# A-GSM.net
KiCad netlist of a schematic drawn in Altium Designer
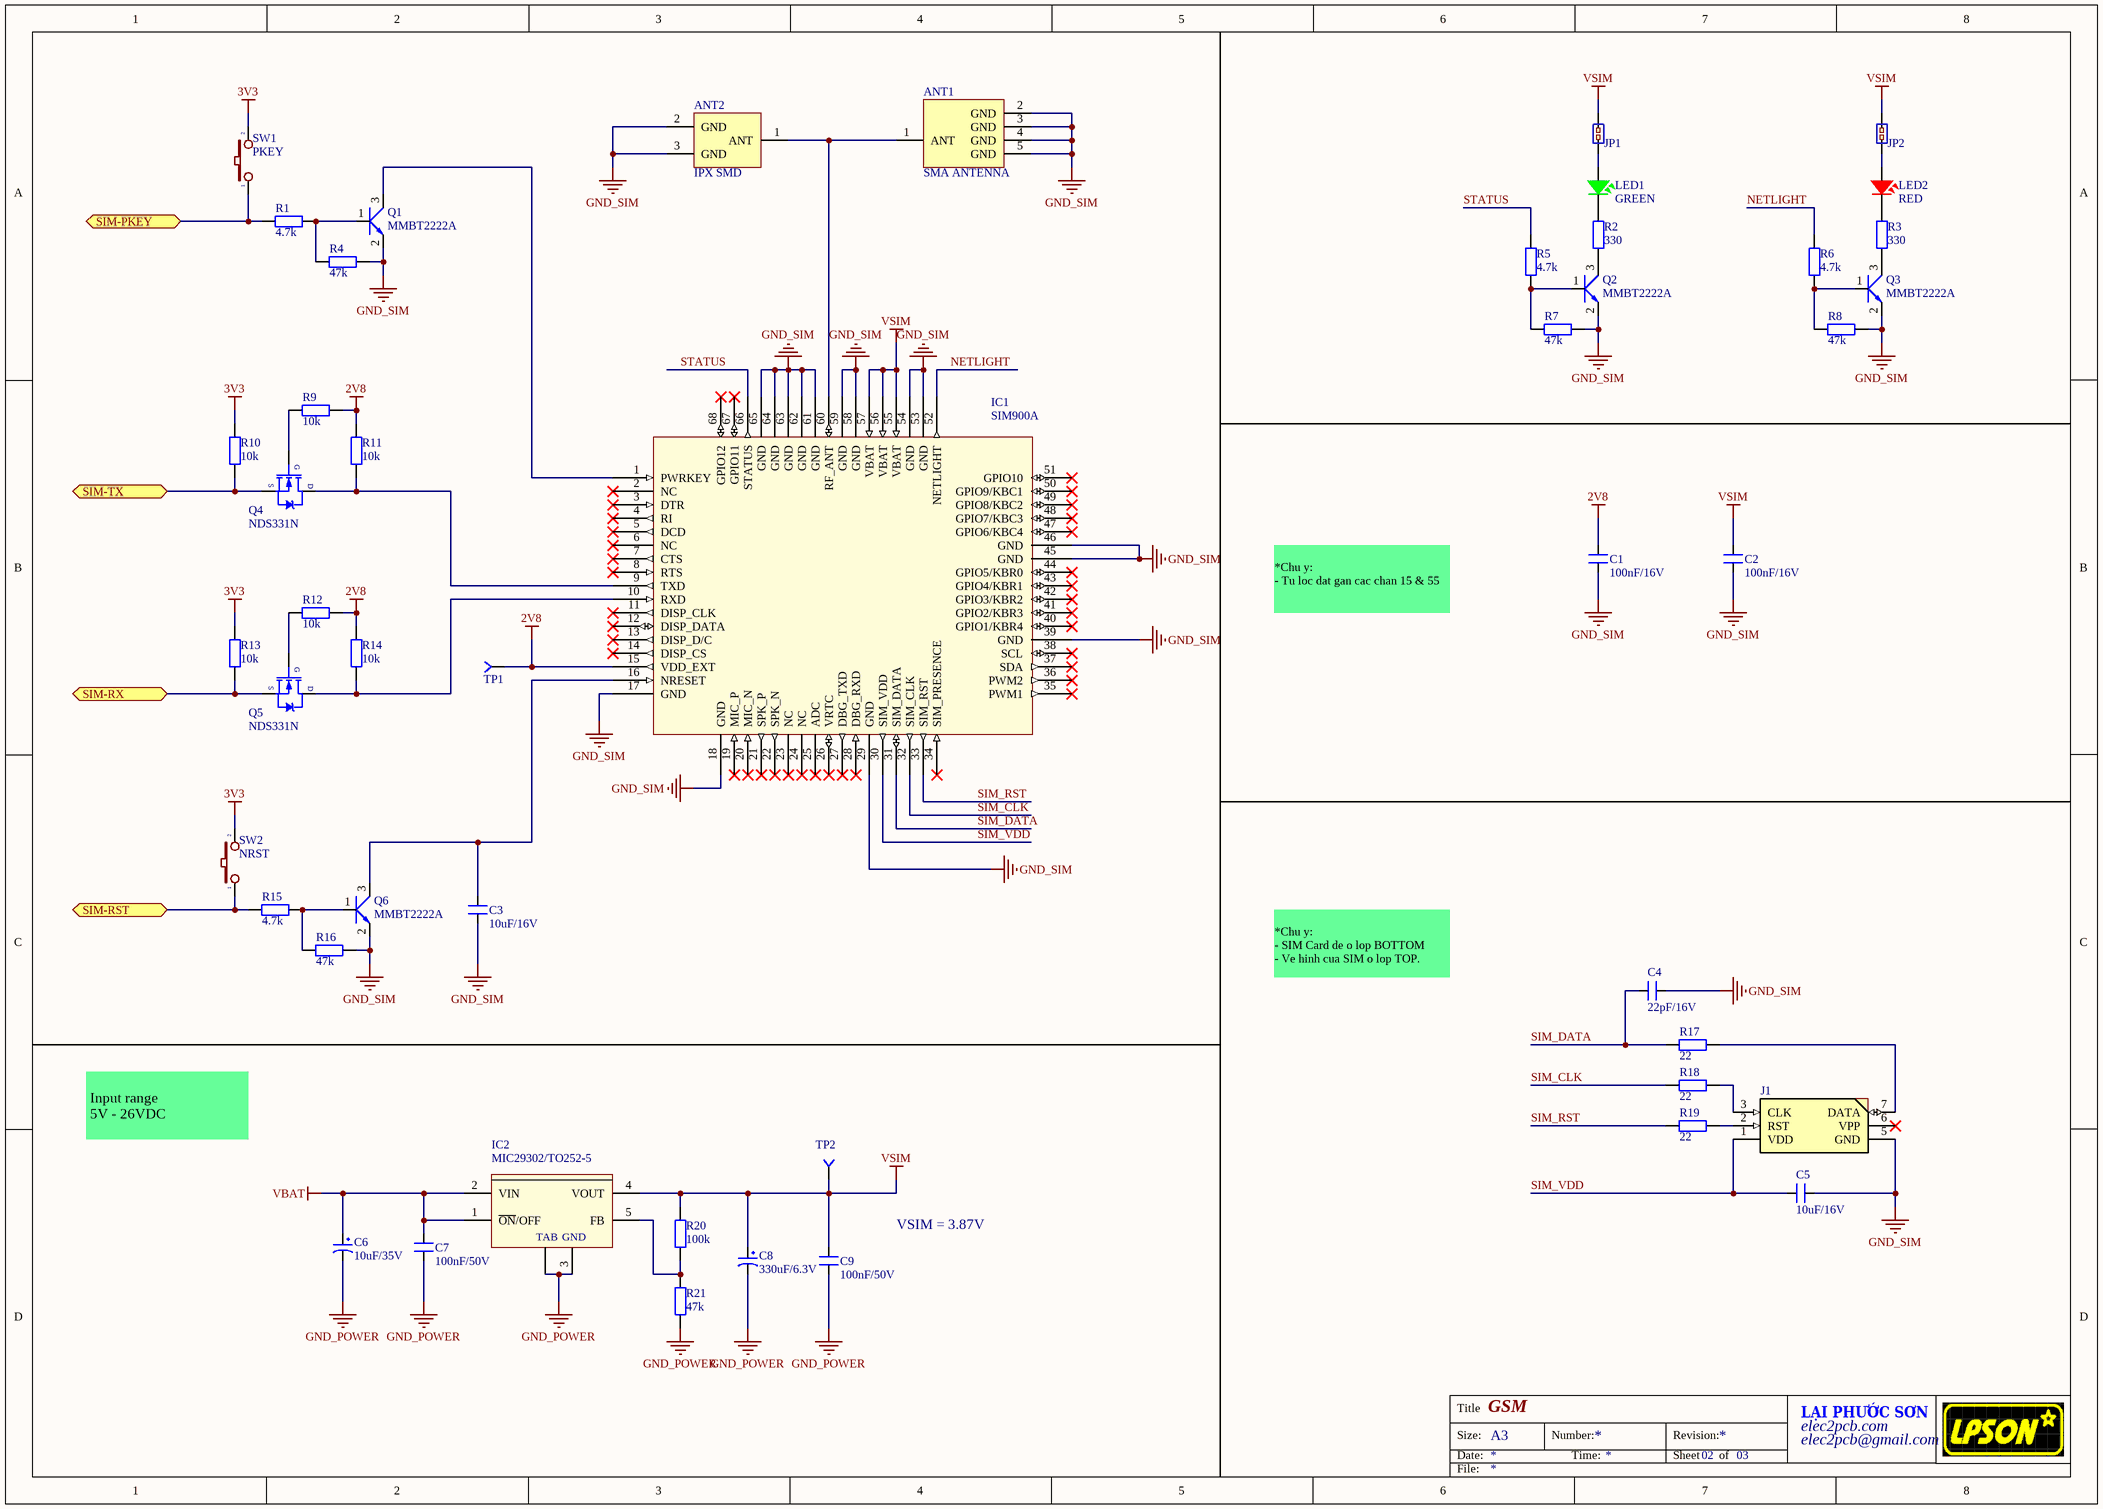
[diagram p0: A-GSM.SchDoc]

(export (version "E")
  (design (tool "Eeschema 10.0.6"))
  (components
    (comp (ref "ANT1")
      (value "SMA ANTENNA")
      (footprint "ANT-SMA-ST-F")
      (description "SMA Right-Angle PCB Female Antenna")
      (fields (field (name "Comment") "ANTEN-SMA"))
      (libsource (lib "Tran Tuan") (part "ANTEN-SMA"))
    )
    (comp (ref "ANT2")
      (value "IPX SMD")
      (footprint "ANT-IPX-SMD")
      (description "IPX, SMD, ANTENNA")
      (fields (field (name "Comment") "ANTEN-IPX"))
      (libsource (lib "Tran Tuan") (part "ANTEN-IPX"))
    )
    (comp (ref "C1")
      (value "100nF/16V")
      (footprint "C0805-2012")
      (description "CAP CER 0.1UF 16V X7R 0805")
      (fields
        (field (name "MANUFACTURER") "Kemet")
        (field (name "MANUFACTURER PART NUMBER") "C0805C104K4RACTU")
      )
      (libsource (lib "Tran Tuan") (part "CAP-CER/100nF/16V/X7R/0805"))
    )
    (comp (ref "C2")
      (value "100nF/16V")
      (footprint "C0805-2012")
      (description "CAP CER 0.1UF 16V X7R 0805")
      (fields
        (field (name "MANUFACTURER") "Kemet")
        (field (name "MANUFACTURER PART NUMBER") "C0805C104K4RACTU")
      )
      (libsource (lib "Tran Tuan") (part "CAP-CER/100nF/16V/X7R/0805"))
    )
    (comp (ref "C3")
      (value "10uF/16V")
      (footprint "C0805-2012")
      (description "CAP CER 10UF 16V X5R 0805")
      (fields
        (field (name "MANUFACTURER") "Murata Electronics North America")
        (field (name "MANUFACTURER PART NUMBER") "GRM21BR61C106KE15L")
      )
      (libsource (lib "Tran Tuan") (part "CAP-CER/10UF/16V/X5R/0805"))
    )
    (comp (ref "C4")
      (value "22pF/16V")
      (footprint "C0603-1608")
      (description "CAP CER 22PF 16V NP0 0603")
      (fields
        (field (name "MANUFACTURER") "Kemet")
        (field (name "MANUFACTURER PART NUMBER") "C0603C220K4GACTU")
      )
      (libsource (lib "Tran Tuan") (part "CAP-CER/22pF/16V/NP0/0603"))
    )
    (comp (ref "C5")
      (value "10uF/16V")
      (footprint "C0805-2012")
      (description "CAP CER 10UF 16V X5R 0805")
      (fields
        (field (name "MANUFACTURER") "Murata Electronics North America")
        (field (name "MANUFACTURER PART NUMBER") "GRM21BR61C106KE15L")
      )
      (libsource (lib "Tran Tuan") (part "CAP-CER/10UF/16V/X5R/0805"))
    )
    (comp (ref "C6")
      (value "10uF/35V")
      (footprint "CAP_TANTA_10UF_35V")
      (description "CAP TANT 10UF 35V 10% 2413")
      (fields
        (field (name "MANUFACTURER") "Kemet")
        (field (name "MANUFACTURER PART NUMBER") "T491C106K035AT")
      )
      (libsource (lib "Tran Tuan") (part "CAP-TANT/10uF/35V/2413"))
    )
    (comp (ref "C7")
      (value "100nF/50V")
      (footprint "C0805-2012")
      (description "CAP CER 0.1UF 50V X7R 0805")
      (fields
        (field (name "MANUFACTURER") "AVX Corporation")
        (field (name "MANUFACTURER PART NUMBER") "08055C104KAT2A")
      )
      (libsource (lib "Tran Tuan") (part "CAP-CER/100nF/50V/X7R/0805"))
    )
    (comp (ref "C8")
      (value "330uF/6.3V")
      (footprint "CAP_TANTA-3528")
      (description "CAP TAN 330UF 20% 6V 3528-21")
      (fields
        (field (name "MANUFACTURER") "Kemet")
        (field (name "MANUFACTURER PART NUMBER") "T490B337M006ATE800")
      )
      (libsource (lib "Tran Tuan") (part "CAP-TANT/330uF/6.3V/3528"))
    )
    (comp (ref "C9")
      (value "100nF/50V")
      (footprint "C0805-2012")
      (description "CAP CER 0.1UF 50V X7R 0805")
      (fields
        (field (name "MANUFACTURER") "AVX Corporation")
        (field (name "MANUFACTURER PART NUMBER") "08055C104KAT2A")
      )
      (libsource (lib "Tran Tuan") (part "CAP-CER/100nF/50V/X7R/0805"))
    )
    (comp (ref "IC1")
      (value "SIM900A/SIMCOM")
      (footprint "SIM900A")
      (description "SIM900A, Dual-band GSM/GPRS 900/1800MHz Module")
      (fields (field (name "MANUFACTURER") "SIMCOM") (field (name "MANUFACTURER PART NUMBER") "SIM900A"))
      (libsource (lib "Tran Tuan") (part "SIM900A/SIMCOM"))
    )
    (comp (ref "IC2")
      (value "MIC29302/TO252-5")
      (footprint "MIC29302A")
      (description "IC REG LDO ADJ 3A TO252-5")
      (fields
        (field (name "MANUFACTURER") "Microchip Technology")
        (field (name "MANUFACTURER PART NUMBER") "MIC29302AWD-TR")
      )
      (libsource (lib "Tran Tuan") (part "MIC29302/TO252-5"))
    )
    (comp (ref "J1")
      (value "SIM-FMS006-2620-0")
      (footprint "SIM-FMS006-2620-0")
      (description "SIM Card Conn 6-Pin Top, Mount, Push-Push")
      (libsource (lib "Tran Tuan") (part "SIM-FMS006-2620-0"))
    )
    (comp (ref "JP1")
      (value "JP2-ShortingJumper")
      (footprint "Header_2")
      (description "2.54mm 2-Pin Shorting Jumper")
      (libsource (lib "Tran Tuan") (part "JP2-ShortingJumper"))
    )
    (comp (ref "JP2")
      (value "JP2-ShortingJumper")
      (footprint "Header_2")
      (description "2.54mm 2-Pin Shorting Jumper")
      (libsource (lib "Tran Tuan") (part "JP2-ShortingJumper"))
    )
    (comp (ref "LED1")
      (value "GREEN")
      (footprint "Led 0805G")
      (description "LED GREEN CLEAR 0805 SMD")
      (fields
        (field (name "MANUFACTURER") "Lite-On Inc.")
        (field (name "MANUFACTURER PART NUMBER") "LTST-C171GKT")
      )
      (libsource (lib "Tran Tuan") (part "LED-GREEN/CLEAR/0805"))
    )
    (comp (ref "LED2")
      (value "RED")
      (footprint "Led 0805R")
      (description "LED RED CLEAR 0805 SMD")
      (fields
        (field (name "MANUFACTURER") "Lite-On Inc.")
        (field (name "MANUFACTURER PART NUMBER") "LTST-C171KRKT")
      )
      (libsource (lib "Tran Tuan") (part "LED-RED/CLEAR/0805"))
    )
    (comp (ref "Q1")
      (value "MMBT2222A")
      (footprint "MMBT2222A")
      (description "TRANS NPN 40V 0.6A SOT23")
      (fields
        (field (name "MANUFACTURER") "ON Semiconductor")
        (field (name "MANUFACTURER PART NUMBER") "MMBT2222ALT1G")
      )
      (libsource (lib "Tran Tuan") (part "BJT-MMBT2222A/SOT23"))
    )
    (comp (ref "Q2")
      (value "MMBT2222A")
      (footprint "MMBT2222A")
      (description "TRANS NPN 40V 0.6A SOT23")
      (fields
        (field (name "MANUFACTURER") "ON Semiconductor")
        (field (name "MANUFACTURER PART NUMBER") "MMBT2222ALT1G")
      )
      (libsource (lib "Tran Tuan") (part "BJT-MMBT2222A/SOT23"))
    )
    (comp (ref "Q3")
      (value "MMBT2222A")
      (footprint "MMBT2222A")
      (description "TRANS NPN 40V 0.6A SOT23")
      (fields
        (field (name "MANUFACTURER") "ON Semiconductor")
        (field (name "MANUFACTURER PART NUMBER") "MMBT2222ALT1G")
      )
      (libsource (lib "Tran Tuan") (part "BJT-MMBT2222A/SOT23"))
    )
    (comp (ref "Q4")
      (value "NDS331N")
      (footprint "NDS331N")
      (description "MOSFET N-CH 20V 1.3A SSOT3")
      (fields (field (name "MANUFACTURER") "Fairchild Semiconductor"))
      (libsource (lib "Tran Tuan") (part "MOSFET-NDS331N/SSOT3"))
    )
    (comp (ref "Q5")
      (value "NDS331N")
      (footprint "NDS331N")
      (description "MOSFET N-CH 20V 1.3A SSOT3")
      (fields (field (name "MANUFACTURER") "Fairchild Semiconductor"))
      (libsource (lib "Tran Tuan") (part "MOSFET-NDS331N/SSOT3"))
    )
    (comp (ref "Q6")
      (value "MMBT2222A")
      (footprint "MMBT2222A")
      (description "TRANS NPN 40V 0.6A SOT23")
      (fields
        (field (name "MANUFACTURER") "ON Semiconductor")
        (field (name "MANUFACTURER PART NUMBER") "MMBT2222ALT1G")
      )
      (libsource (lib "Tran Tuan") (part "BJT-MMBT2222A/SOT23"))
    )
    (comp (ref "R1")
      (value "~")
      (footprint "RESC2012(0805)")
      (description "RES SMD 4.7K OHM 5% 1/8W 0805")
      (fields
        (field (name "MANUFACTURER") "Yageo")
        (field (name "MANUFACTURER PART NUMBER") "RC0805JR-074K7L")
        (field (name "RESISTANCE (OHMS)") "4.7k")
      )
      (libsource (lib "") (part "RES-0805/±5%_3"))
    )
    (comp (ref "R2")
      (value "~")
      (footprint "RESC2012(0805)")
      (description "RES SMD 330 OHM 5% 1/8W 0805")
      (fields
        (field (name "MANUFACTURER") "Yageo")
        (field (name "MANUFACTURER PART NUMBER") "RC0805JR-07330RL")
        (field (name "RESISTANCE (OHMS)") "330")
      )
      (libsource (lib "") (part "RES-0805/±5%_2"))
    )
    (comp (ref "R3")
      (value "~")
      (footprint "RESC2012(0805)")
      (description "RES SMD 330 OHM 5% 1/8W 0805")
      (fields
        (field (name "MANUFACTURER") "Yageo")
        (field (name "MANUFACTURER PART NUMBER") "RC0805JR-07330RL")
        (field (name "RESISTANCE (OHMS)") "330")
      )
      (libsource (lib "") (part "RES-0805/±5%_2"))
    )
    (comp (ref "R4")
      (value "~")
      (footprint "RESC2012(0805)")
      (description "RES SMD 47K OHM 5% 1/8W 0805")
      (fields
        (field (name "MANUFACTURER") "Yageo")
        (field (name "MANUFACTURER PART NUMBER") "RC0805JR-0747KL")
        (field (name "RESISTANCE (OHMS)") "47k")
      )
      (libsource (lib "") (part "RES-0805/±5%_3"))
    )
    (comp (ref "R5")
      (value "~")
      (footprint "RESC2012(0805)")
      (description "RES SMD 4.7K OHM 5% 1/8W 0805")
      (fields
        (field (name "MANUFACTURER") "Yageo")
        (field (name "MANUFACTURER PART NUMBER") "RC0805JR-074K7L")
        (field (name "RESISTANCE (OHMS)") "4.7k")
      )
      (libsource (lib "") (part "RES-0805/±5%_2"))
    )
    (comp (ref "R6")
      (value "~")
      (footprint "RESC2012(0805)")
      (description "RES SMD 4.7K OHM 5% 1/8W 0805")
      (fields
        (field (name "MANUFACTURER") "Yageo")
        (field (name "MANUFACTURER PART NUMBER") "RC0805JR-074K7L")
        (field (name "RESISTANCE (OHMS)") "4.7k")
      )
      (libsource (lib "") (part "RES-0805/±5%_2"))
    )
    (comp (ref "R7")
      (value "~")
      (footprint "RESC2012(0805)")
      (description "RES SMD 47K OHM 5% 1/8W 0805")
      (fields
        (field (name "MANUFACTURER") "Yageo")
        (field (name "MANUFACTURER PART NUMBER") "RC0805JR-0747KL")
        (field (name "RESISTANCE (OHMS)") "47k")
      )
      (libsource (lib "") (part "RES-0805/±5%_3"))
    )
    (comp (ref "R8")
      (value "~")
      (footprint "RESC2012(0805)")
      (description "RES SMD 47K OHM 5% 1/8W 0805")
      (fields
        (field (name "MANUFACTURER") "Yageo")
        (field (name "MANUFACTURER PART NUMBER") "RC0805JR-0747KL")
        (field (name "RESISTANCE (OHMS)") "47k")
      )
      (libsource (lib "") (part "RES-0805/±5%_3"))
    )
    (comp (ref "R9")
      (value "~")
      (footprint "RESC2012(0805)")
      (description "RES SMD 10K OHM 5% 1/8W 0805")
      (fields
        (field (name "MANUFACTURER") "Yageo")
        (field (name "MANUFACTURER PART NUMBER") "RC0805JR-0710KL")
        (field (name "RESISTANCE (OHMS)") "10k")
      )
      (libsource (lib "") (part "RES-0805/±5%_3"))
    )
    (comp (ref "R10")
      (value "~")
      (footprint "RESC2012(0805)")
      (description "RES SMD 10K OHM 5% 1/8W 0805")
      (fields
        (field (name "MANUFACTURER") "Yageo")
        (field (name "MANUFACTURER PART NUMBER") "RC0805JR-0710KL")
        (field (name "RESISTANCE (OHMS)") "10k")
      )
      (libsource (lib "Tran Tuan") (part "RES-0805/±5%"))
    )
    (comp (ref "R11")
      (value "~")
      (footprint "RESC2012(0805)")
      (description "RES SMD 10K OHM 5% 1/8W 0805")
      (fields
        (field (name "MANUFACTURER") "Yageo")
        (field (name "MANUFACTURER PART NUMBER") "RC0805JR-0710KL")
        (field (name "RESISTANCE (OHMS)") "10k")
      )
      (libsource (lib "Tran Tuan") (part "RES-0805/±5%"))
    )
    (comp (ref "R12")
      (value "~")
      (footprint "RESC2012(0805)")
      (description "RES SMD 10K OHM 5% 1/8W 0805")
      (fields
        (field (name "MANUFACTURER") "Yageo")
        (field (name "MANUFACTURER PART NUMBER") "RC0805JR-0710KL")
        (field (name "RESISTANCE (OHMS)") "10k")
      )
      (libsource (lib "") (part "RES-0805/±5%_3"))
    )
    (comp (ref "R13")
      (value "~")
      (footprint "RESC2012(0805)")
      (description "RES SMD 10K OHM 5% 1/8W 0805")
      (fields
        (field (name "MANUFACTURER") "Yageo")
        (field (name "MANUFACTURER PART NUMBER") "RC0805JR-0710KL")
        (field (name "RESISTANCE (OHMS)") "10k")
      )
      (libsource (lib "Tran Tuan") (part "RES-0805/±5%"))
    )
    (comp (ref "R14")
      (value "~")
      (footprint "RESC2012(0805)")
      (description "RES SMD 10K OHM 5% 1/8W 0805")
      (fields
        (field (name "MANUFACTURER") "Yageo")
        (field (name "MANUFACTURER PART NUMBER") "RC0805JR-0710KL")
        (field (name "RESISTANCE (OHMS)") "10k")
      )
      (libsource (lib "Tran Tuan") (part "RES-0805/±5%"))
    )
    (comp (ref "R15")
      (value "~")
      (footprint "RESC2012(0805)")
      (description "RES SMD 4.7K OHM 5% 1/8W 0805")
      (fields
        (field (name "MANUFACTURER") "Yageo")
        (field (name "MANUFACTURER PART NUMBER") "RC0805JR-074K7L")
        (field (name "RESISTANCE (OHMS)") "4.7k")
      )
      (libsource (lib "") (part "RES-0805/±5%_3"))
    )
    (comp (ref "R16")
      (value "~")
      (footprint "RESC2012(0805)")
      (description "RES SMD 47K OHM 5% 1/8W 0805")
      (fields
        (field (name "MANUFACTURER") "Yageo")
        (field (name "MANUFACTURER PART NUMBER") "RC0805JR-0747KL")
        (field (name "RESISTANCE (OHMS)") "47k")
      )
      (libsource (lib "") (part "RES-0805/±5%_3"))
    )
    (comp (ref "R17")
      (value "~")
      (footprint "RESC2012(0805)")
      (description "RES SMD 22 OHM 5% 1/8W 0805")
      (fields
        (field (name "MANUFACTURER") "Yageo")
        (field (name "MANUFACTURER PART NUMBER") "RC0805JR-0722RL")
        (field (name "RESISTANCE (OHMS)") "22")
      )
      (libsource (lib "") (part "RES-0805/±5%_1"))
    )
    (comp (ref "R18")
      (value "~")
      (footprint "RESC2012(0805)")
      (description "RES SMD 22 OHM 5% 1/8W 0805")
      (fields
        (field (name "MANUFACTURER") "Yageo")
        (field (name "MANUFACTURER PART NUMBER") "RC0805JR-0722RL")
        (field (name "RESISTANCE (OHMS)") "22")
      )
      (libsource (lib "") (part "RES-0805/±5%_1"))
    )
    (comp (ref "R19")
      (value "~")
      (footprint "RESC2012(0805)")
      (description "RES SMD 22 OHM 5% 1/8W 0805")
      (fields
        (field (name "MANUFACTURER") "Yageo")
        (field (name "MANUFACTURER PART NUMBER") "RC0805JR-0722RL")
        (field (name "RESISTANCE (OHMS)") "22")
      )
      (libsource (lib "") (part "RES-0805/±5%_1"))
    )
    (comp (ref "R20")
      (value "~")
      (footprint "RESC2012(0805)")
      (description "RES SMD 100K OHM 5% 1/8W 0805")
      (fields
        (field (name "MANUFACTURER") "Yageo")
        (field (name "MANUFACTURER PART NUMBER") "RC0805JR-07100KL")
        (field (name "RESISTANCE (OHMS)") "100k")
      )
      (libsource (lib "Tran Tuan") (part "RES-0805/±5%"))
    )
    (comp (ref "R21")
      (value "~")
      (footprint "RESC2012(0805)")
      (description "RES SMD 47K OHM 5% 1/8W 0805")
      (fields
        (field (name "MANUFACTURER") "Yageo")
        (field (name "MANUFACTURER PART NUMBER") "RC0805JR-0747KL")
        (field (name "RESISTANCE (OHMS)") "47k")
      )
      (libsource (lib "") (part "RES-0805/±5%_2"))
    )
    (comp (ref "SW1")
      (value "PKEY")
      (footprint "BTN-EVQ-11A04M")
      (description "SWITCH TACTILE SPST-NO 0.02A 15V")
      (fields
        (field (name "MANUFACTURER") "Panasonic Electronic Components")
        (field (name "MANUFACTURER PART NUMBER") "EVQ-11A04M")
      )
      (libsource (lib "Tran Tuan") (part "SW2-PUSH/SPST/NO"))
    )
    (comp (ref "SW2")
      (value "NRST")
      (footprint "BTN-EVQ-11A04M")
      (description "SWITCH TACTILE SPST-NO 0.02A 15V")
      (fields
        (field (name "MANUFACTURER") "Panasonic Electronic Components")
        (field (name "MANUFACTURER PART NUMBER") "EVQ-11A04M")
      )
      (libsource (lib "Tran Tuan") (part "SW2-PUSH/SPST/NO"))
    )
    (comp (ref "TP1")
      (value "Test Point")
      (footprint "Test_point_VIA06")
      (description "Test Point, Pad, Hole")
      (libsource (lib "Tran Tuan") (part "Connector-TP"))
    )
    (comp (ref "TP2")
      (value "Test Point")
      (footprint "Test_point_VIA06")
      (description "Test Point, Pad, Hole")
      (libsource (lib "Tran Tuan") (part "Connector-TP"))
    )
  )
  (nets
    (net (code "1") (name "/NETLIGHT") (class "Default")
      (node (ref "IC1") (pin "52") (pinfunction "NETLIGHT_52") (pintype "output"))
      (node (ref "R6") (pin "2") (pinfunction "2_2") (pintype "passive"))
    )
    (net (code "2") (name "/SIM-PKEY") (class "Default")
      (node (ref "R1") (pin "1") (pinfunction "1_1") (pintype "passive"))
      (node (ref "SW1") (pin "1") (pinfunction "1_1") (pintype "passive"))
    )
    (net (code "3") (name "/SIM-RST") (class "Default")
      (node (ref "R15") (pin "1") (pinfunction "1_1") (pintype "passive"))
      (node (ref "SW2") (pin "1") (pinfunction "1_1") (pintype "passive"))
    )
    (net (code "4") (name "/SIM-RX") (class "Default")
      (node (ref "Q5") (pin "2") (pinfunction "S_2") (pintype "passive"))
      (node (ref "R13") (pin "2") (pinfunction "2_2") (pintype "passive"))
    )
    (net (code "5") (name "/SIM-TX") (class "Default")
      (node (ref "Q4") (pin "2") (pinfunction "S_2") (pintype "passive"))
      (node (ref "R10") (pin "2") (pinfunction "2_2") (pintype "passive"))
    )
    (net (code "6") (name "/SIM_CLK") (class "Default")
      (node (ref "IC1") (pin "32") (pinfunction "SIM_CLK_32") (pintype "output"))
      (node (ref "R18") (pin "2") (pinfunction "2_2") (pintype "passive"))
    )
    (net (code "7") (name "/SIM_DATA") (class "Default")
      (node (ref "C4") (pin "1") (pinfunction "1_1") (pintype "passive"))
      (node (ref "IC1") (pin "31") (pinfunction "SIM_DATA_31") (pintype "bidirectional"))
      (node (ref "R17") (pin "2") (pinfunction "2_2") (pintype "passive"))
    )
    (net (code "8") (name "/SIM_RST") (class "Default")
      (node (ref "IC1") (pin "33") (pinfunction "SIM_RST_33") (pintype "output"))
      (node (ref "R19") (pin "2") (pinfunction "2_2") (pintype "passive"))
    )
    (net (code "9") (name "/SIM_VDD") (class "Default")
      (node (ref "C5") (pin "1") (pinfunction "1_1") (pintype "passive"))
      (node (ref "IC1") (pin "30") (pinfunction "SIM_VDD_30") (pintype "output"))
      (node (ref "J1") (pin "1") (pinfunction "VDD_1") (pintype "passive"))
    )
    (net (code "10") (name "/STATUS") (class "Default")
      (node (ref "IC1") (pin "66") (pinfunction "STATUS_66") (pintype "output"))
      (node (ref "R5") (pin "2") (pinfunction "2_2") (pintype "passive"))
    )
    (net (code "11") (name "2V8") (class "Default")
      (node (ref "C1") (pin "1") (pinfunction "1_1") (pintype "passive"))
      (node (ref "IC1") (pin "15") (pinfunction "VDD_EXT_15") (pintype "output"))
      (node (ref "R11") (pin "1") (pinfunction "1_1") (pintype "passive"))
      (node (ref "R12") (pin "2") (pinfunction "2_2") (pintype "passive"))
      (node (ref "R14") (pin "1") (pinfunction "1_1") (pintype "passive"))
      (node (ref "R9") (pin "2") (pinfunction "2_2") (pintype "passive"))
      (node (ref "TP1") (pin "1") (pinfunction "1_1") (pintype "passive"))
    )
    (net (code "12") (name "3V3") (class "Default")
      (node (ref "R10") (pin "1") (pinfunction "1_1") (pintype "passive"))
      (node (ref "R13") (pin "1") (pinfunction "1_1") (pintype "passive"))
      (node (ref "SW1") (pin "2") (pinfunction "2_2") (pintype "passive"))
      (node (ref "SW2") (pin "2") (pinfunction "2_2") (pintype "passive"))
    )
    (net (code "13") (name "GND_POWER") (class "Default")
      (node (ref "C6") (pin "2") (pinfunction "2_2") (pintype "passive"))
      (node (ref "C7") (pin "2") (pinfunction "2_2") (pintype "passive"))
      (node (ref "C8") (pin "2") (pinfunction "2_2") (pintype "passive"))
      (node (ref "C9") (pin "2") (pinfunction "2_2") (pintype "passive"))
      (node (ref "IC2") (pin "3") (pinfunction "GND_3") (pintype "power_in"))
      (node (ref "IC2") (pin "6") (pinfunction "TAB_6") (pintype "power_in"))
      (node (ref "R21") (pin "1") (pinfunction "1_1") (pintype "passive"))
    )
    (net (code "14") (name "GND_SIM") (class "Default")
      (node (ref "ANT1") (pin "2") (pinfunction "GND_2") (pintype "power_in"))
      (node (ref "ANT1") (pin "3") (pinfunction "GND_3") (pintype "power_in"))
      (node (ref "ANT1") (pin "4") (pinfunction "GND_4") (pintype "power_in"))
      (node (ref "ANT1") (pin "5") (pinfunction "GND_5") (pintype "power_in"))
      (node (ref "ANT2") (pin "2") (pinfunction "GND_2") (pintype "power_in"))
      (node (ref "ANT2") (pin "3") (pinfunction "GND_3") (pintype "power_in"))
      (node (ref "C1") (pin "2") (pinfunction "2_2") (pintype "passive"))
      (node (ref "C2") (pin "2") (pinfunction "2_2") (pintype "passive"))
      (node (ref "C3") (pin "2") (pinfunction "2_2") (pintype "passive"))
      (node (ref "C4") (pin "2") (pinfunction "2_2") (pintype "passive"))
      (node (ref "C5") (pin "2") (pinfunction "2_2") (pintype "passive"))
      (node (ref "IC1") (pin "17") (pinfunction "GND_17") (pintype "power_in"))
      (node (ref "IC1") (pin "18") (pinfunction "GND_18") (pintype "power_in"))
      (node (ref "IC1") (pin "29") (pinfunction "GND_29") (pintype "power_in"))
      (node (ref "IC1") (pin "39") (pinfunction "GND_39") (pintype "power_in"))
      (node (ref "IC1") (pin "45") (pinfunction "GND_45") (pintype "power_in"))
      (node (ref "IC1") (pin "46") (pinfunction "GND_46") (pintype "power_in"))
      (node (ref "IC1") (pin "53") (pinfunction "GND_53") (pintype "power_in"))
      (node (ref "IC1") (pin "54") (pinfunction "GND_54") (pintype "power_in"))
      (node (ref "IC1") (pin "58") (pinfunction "GND_58") (pintype "power_in"))
      (node (ref "IC1") (pin "59") (pinfunction "GND_59") (pintype "power_in"))
      (node (ref "IC1") (pin "61") (pinfunction "GND_61") (pintype "power_in"))
      (node (ref "IC1") (pin "62") (pinfunction "GND_62") (pintype "power_in"))
      (node (ref "IC1") (pin "63") (pinfunction "GND_63") (pintype "power_in"))
      (node (ref "IC1") (pin "64") (pinfunction "GND_64") (pintype "power_in"))
      (node (ref "IC1") (pin "65") (pinfunction "GND_65") (pintype "power_in"))
      (node (ref "J1") (pin "5") (pinfunction "GND_5") (pintype "passive"))
      (node (ref "Q1") (pin "2") (pinfunction "E_2") (pintype "passive"))
      (node (ref "Q2") (pin "2") (pinfunction "E_2") (pintype "passive"))
      (node (ref "Q3") (pin "2") (pinfunction "E_2") (pintype "passive"))
      (node (ref "Q6") (pin "2") (pinfunction "E_2") (pintype "passive"))
      (node (ref "R16") (pin "2") (pinfunction "2_2") (pintype "passive"))
      (node (ref "R4") (pin "2") (pinfunction "2_2") (pintype "passive"))
      (node (ref "R7") (pin "2") (pinfunction "2_2") (pintype "passive"))
      (node (ref "R8") (pin "2") (pinfunction "2_2") (pintype "passive"))
    )
    (net (code "15") (name "Net-(ANT1-ANT)") (class "Default")
      (node (ref "ANT1") (pin "1") (pinfunction "ANT_1") (pintype "passive"))
      (node (ref "ANT2") (pin "1") (pinfunction "ANT_1") (pintype "passive"))
      (node (ref "IC1") (pin "60") (pinfunction "RF_ANT_60") (pintype "bidirectional"))
    )
    (net (code "16") (name "Net-(IC1-NRESET)") (class "Default")
      (node (ref "C3") (pin "1") (pinfunction "1_1") (pintype "passive"))
      (node (ref "IC1") (pin "16") (pinfunction "NRESET_16") (pintype "input"))
      (node (ref "Q6") (pin "3") (pinfunction "C_3") (pintype "passive"))
    )
    (net (code "17") (name "Net-(IC1-PWRKEY)") (class "Default")
      (node (ref "IC1") (pin "1") (pinfunction "PWRKEY_1") (pintype "input"))
      (node (ref "Q1") (pin "3") (pinfunction "C_3") (pintype "passive"))
    )
    (net (code "18") (name "Net-(IC1-RXD)") (class "Default")
      (node (ref "IC1") (pin "10") (pinfunction "RXD_10") (pintype "input"))
      (node (ref "Q5") (pin "3") (pinfunction "D_3") (pintype "passive"))
      (node (ref "R14") (pin "2") (pinfunction "2_2") (pintype "passive"))
    )
    (net (code "19") (name "Net-(IC1-TXD)") (class "Default")
      (node (ref "IC1") (pin "9") (pinfunction "TXD_9") (pintype "output"))
      (node (ref "Q4") (pin "3") (pinfunction "D_3") (pintype "passive"))
      (node (ref "R11") (pin "2") (pinfunction "2_2") (pintype "passive"))
    )
    (net (code "20") (name "Net-(IC2-FB)") (class "Default")
      (node (ref "IC2") (pin "5") (pinfunction "FB_5") (pintype "power_in"))
      (node (ref "R20") (pin "2") (pinfunction "2_2") (pintype "passive"))
      (node (ref "R21") (pin "2") (pinfunction "2_2") (pintype "passive"))
    )
    (net (code "21") (name "Net-(J1-CLK)") (class "Default")
      (node (ref "J1") (pin "3") (pinfunction "CLK_3") (pintype "input"))
      (node (ref "R18") (pin "1") (pinfunction "1_1") (pintype "passive"))
    )
    (net (code "22") (name "Net-(J1-DATA)") (class "Default")
      (node (ref "J1") (pin "7") (pinfunction "DATA_7") (pintype "bidirectional"))
      (node (ref "R17") (pin "1") (pinfunction "1_1") (pintype "passive"))
    )
    (net (code "23") (name "Net-(J1-RST)") (class "Default")
      (node (ref "J1") (pin "2") (pinfunction "RST_2") (pintype "input"))
      (node (ref "R19") (pin "1") (pinfunction "1_1") (pintype "passive"))
    )
    (net (code "24") (name "Net-(LED1-A)") (class "Default")
      (node (ref "JP1") (pin "1") (pinfunction "1_1") (pintype "passive"))
      (node (ref "LED1") (pin "1") (pinfunction "A_1") (pintype "passive"))
    )
    (net (code "25") (name "Net-(LED1-K)") (class "Default")
      (node (ref "LED1") (pin "2") (pinfunction "K_2") (pintype "passive"))
      (node (ref "R2") (pin "2") (pinfunction "2_2") (pintype "passive"))
    )
    (net (code "26") (name "Net-(LED2-A)") (class "Default")
      (node (ref "JP2") (pin "1") (pinfunction "1_1") (pintype "passive"))
      (node (ref "LED2") (pin "1") (pinfunction "A_1") (pintype "passive"))
    )
    (net (code "27") (name "Net-(LED2-K)") (class "Default")
      (node (ref "LED2") (pin "2") (pinfunction "K_2") (pintype "passive"))
      (node (ref "R3") (pin "2") (pinfunction "2_2") (pintype "passive"))
    )
    (net (code "28") (name "Net-(Q1-B)") (class "Default")
      (node (ref "Q1") (pin "1") (pinfunction "B_1") (pintype "passive"))
      (node (ref "R1") (pin "2") (pinfunction "2_2") (pintype "passive"))
      (node (ref "R4") (pin "1") (pinfunction "1_1") (pintype "passive"))
    )
    (net (code "29") (name "Net-(Q2-B)") (class "Default")
      (node (ref "Q2") (pin "1") (pinfunction "B_1") (pintype "passive"))
      (node (ref "R5") (pin "1") (pinfunction "1_1") (pintype "passive"))
      (node (ref "R7") (pin "1") (pinfunction "1_1") (pintype "passive"))
    )
    (net (code "30") (name "Net-(Q2-C)") (class "Default")
      (node (ref "Q2") (pin "3") (pinfunction "C_3") (pintype "passive"))
      (node (ref "R2") (pin "1") (pinfunction "1_1") (pintype "passive"))
    )
    (net (code "31") (name "Net-(Q3-B)") (class "Default")
      (node (ref "Q3") (pin "1") (pinfunction "B_1") (pintype "passive"))
      (node (ref "R6") (pin "1") (pinfunction "1_1") (pintype "passive"))
      (node (ref "R8") (pin "1") (pinfunction "1_1") (pintype "passive"))
    )
    (net (code "32") (name "Net-(Q3-C)") (class "Default")
      (node (ref "Q3") (pin "3") (pinfunction "C_3") (pintype "passive"))
      (node (ref "R3") (pin "1") (pinfunction "1_1") (pintype "passive"))
    )
    (net (code "33") (name "Net-(Q4-G)") (class "Default")
      (node (ref "Q4") (pin "1") (pinfunction "G_1") (pintype "passive"))
      (node (ref "R9") (pin "1") (pinfunction "1_1") (pintype "passive"))
    )
    (net (code "34") (name "Net-(Q5-G)") (class "Default")
      (node (ref "Q5") (pin "1") (pinfunction "G_1") (pintype "passive"))
      (node (ref "R12") (pin "1") (pinfunction "1_1") (pintype "passive"))
    )
    (net (code "35") (name "Net-(Q6-B)") (class "Default")
      (node (ref "Q6") (pin "1") (pinfunction "B_1") (pintype "passive"))
      (node (ref "R15") (pin "2") (pinfunction "2_2") (pintype "passive"))
      (node (ref "R16") (pin "1") (pinfunction "1_1") (pintype "passive"))
    )
    (net (code "36") (name "VBAT") (class "Default")
      (node (ref "C6") (pin "1") (pinfunction "1_1") (pintype "passive"))
      (node (ref "C7") (pin "1") (pinfunction "1_1") (pintype "passive"))
      (node (ref "IC2") (pin "1") (pinfunction "~{ON}/OFF_1") (pintype "power_in"))
      (node (ref "IC2") (pin "2") (pinfunction "VIN_2") (pintype "power_in"))
    )
    (net (code "37") (name "VSIM") (class "Default")
      (node (ref "C2") (pin "1") (pinfunction "1_1") (pintype "passive"))
      (node (ref "C8") (pin "1") (pinfunction "1_1") (pintype "passive"))
      (node (ref "C9") (pin "1") (pinfunction "1_1") (pintype "passive"))
      (node (ref "IC1") (pin "55") (pinfunction "VBAT_55") (pintype "input"))
      (node (ref "IC1") (pin "56") (pinfunction "VBAT_56") (pintype "input"))
      (node (ref "IC1") (pin "57") (pinfunction "VBAT_57") (pintype "input"))
      (node (ref "IC2") (pin "4") (pinfunction "VOUT_4") (pintype "power_in"))
      (node (ref "JP1") (pin "2") (pinfunction "2_2") (pintype "passive"))
      (node (ref "JP2") (pin "2") (pinfunction "2_2") (pintype "passive"))
      (node (ref "R20") (pin "1") (pinfunction "1_1") (pintype "passive"))
      (node (ref "TP2") (pin "1") (pinfunction "1_1") (pintype "passive"))
    )
    (net (code "38") (name "unconnected-(IC1-ADC-Pad25)") (class "Default")
      (node (ref "IC1") (pin "25") (pinfunction "ADC_25") (pintype "passive+no_connect"))
    )
    (net (code "39") (name "unconnected-(IC1-CTS-Pad7)") (class "Default")
      (node (ref "IC1") (pin "7") (pinfunction "CTS_7") (pintype "output+no_connect"))
    )
    (net (code "40") (name "unconnected-(IC1-DBG_RXD-Pad28)") (class "Default")
      (node (ref "IC1") (pin "28") (pinfunction "DBG_RXD_28") (pintype "input+no_connect"))
    )
    (net (code "41") (name "unconnected-(IC1-DBG_TXD-Pad27)") (class "Default")
      (node (ref "IC1") (pin "27") (pinfunction "DBG_TXD_27") (pintype "output+no_connect"))
    )
    (net (code "42") (name "unconnected-(IC1-DCD-Pad5)") (class "Default")
      (node (ref "IC1") (pin "5") (pinfunction "DCD_5") (pintype "output+no_connect"))
    )
    (net (code "43") (name "unconnected-(IC1-DISP_CLK-Pad11)") (class "Default")
      (node (ref "IC1") (pin "11") (pinfunction "DISP_CLK_11") (pintype "output+no_connect"))
    )
    (net (code "44") (name "unconnected-(IC1-DISP_CS-Pad14)") (class "Default")
      (node (ref "IC1") (pin "14") (pinfunction "DISP_CS_14") (pintype "output+no_connect"))
    )
    (net (code "45") (name "unconnected-(IC1-DISP_DATA-Pad12)") (class "Default")
      (node (ref "IC1") (pin "12") (pinfunction "DISP_DATA_12") (pintype "bidirectional+no_connect"))
    )
    (net (code "46") (name "unconnected-(IC1-DISP_D{slash}C-Pad13)") (class "Default")
      (node (ref "IC1") (pin "13") (pinfunction "DISP_D/C_13") (pintype "output+no_connect"))
    )
    (net (code "47") (name "unconnected-(IC1-DTR-Pad3)") (class "Default")
      (node (ref "IC1") (pin "3") (pinfunction "DTR_3") (pintype "input+no_connect"))
    )
    (net (code "48") (name "unconnected-(IC1-GPIO1{slash}KBR4-Pad40)") (class "Default")
      (node (ref "IC1") (pin "40") (pinfunction "GPIO1/KBR4_40") (pintype "bidirectional+no_connect"))
    )
    (net (code "49") (name "unconnected-(IC1-GPIO2{slash}KBR3-Pad41)") (class "Default")
      (node (ref "IC1") (pin "41") (pinfunction "GPIO2/KBR3_41") (pintype "bidirectional+no_connect"))
    )
    (net (code "50") (name "unconnected-(IC1-GPIO3{slash}KBR2-Pad42)") (class "Default")
      (node (ref "IC1") (pin "42") (pinfunction "GPIO3/KBR2_42") (pintype "bidirectional+no_connect"))
    )
    (net (code "51") (name "unconnected-(IC1-GPIO4{slash}KBR1-Pad43)") (class "Default")
      (node (ref "IC1") (pin "43") (pinfunction "GPIO4/KBR1_43") (pintype "bidirectional+no_connect"))
    )
    (net (code "52") (name "unconnected-(IC1-GPIO5{slash}KBR0-Pad44)") (class "Default")
      (node (ref "IC1") (pin "44") (pinfunction "GPIO5/KBR0_44") (pintype "bidirectional+no_connect"))
    )
    (net (code "53") (name "unconnected-(IC1-GPIO6{slash}KBC4-Pad47)") (class "Default")
      (node (ref "IC1") (pin "47") (pinfunction "GPIO6/KBC4_47") (pintype "bidirectional+no_connect"))
    )
    (net (code "54") (name "unconnected-(IC1-GPIO7{slash}KBC3-Pad48)") (class "Default")
      (node (ref "IC1") (pin "48") (pinfunction "GPIO7/KBC3_48") (pintype "bidirectional+no_connect"))
    )
    (net (code "55") (name "unconnected-(IC1-GPIO8{slash}KBC2-Pad49)") (class "Default")
      (node (ref "IC1") (pin "49") (pinfunction "GPIO8/KBC2_49") (pintype "bidirectional+no_connect"))
    )
    (net (code "56") (name "unconnected-(IC1-GPIO9{slash}KBC1-Pad50)") (class "Default")
      (node (ref "IC1") (pin "50") (pinfunction "GPIO9/KBC1_50") (pintype "bidirectional+no_connect"))
    )
    (net (code "57") (name "unconnected-(IC1-GPIO10-Pad51)") (class "Default")
      (node (ref "IC1") (pin "51") (pinfunction "GPIO10_51") (pintype "bidirectional+no_connect"))
    )
    (net (code "58") (name "unconnected-(IC1-GPIO11-Pad67)") (class "Default")
      (node (ref "IC1") (pin "67") (pinfunction "GPIO11_67") (pintype "bidirectional+no_connect"))
    )
    (net (code "59") (name "unconnected-(IC1-GPIO12-Pad68)") (class "Default")
      (node (ref "IC1") (pin "68") (pinfunction "GPIO12_68") (pintype "bidirectional+no_connect"))
    )
    (net (code "60") (name "unconnected-(IC1-MIC_N-Pad20)") (class "Default")
      (node (ref "IC1") (pin "20") (pinfunction "MIC_N_20") (pintype "input+no_connect"))
    )
    (net (code "61") (name "unconnected-(IC1-MIC_P-Pad19)") (class "Default")
      (node (ref "IC1") (pin "19") (pinfunction "MIC_P_19") (pintype "input+no_connect"))
    )
    (net (code "62") (name "unconnected-(IC1-NC-Pad2)") (class "Default")
      (node (ref "IC1") (pin "2") (pinfunction "NC_2") (pintype "tri_state+no_connect"))
    )
    (net (code "63") (name "unconnected-(IC1-NC-Pad6)") (class "Default")
      (node (ref "IC1") (pin "6") (pinfunction "NC_6") (pintype "tri_state+no_connect"))
    )
    (net (code "64") (name "unconnected-(IC1-NC-Pad23)") (class "Default")
      (node (ref "IC1") (pin "23") (pinfunction "NC_23") (pintype "tri_state+no_connect"))
    )
    (net (code "65") (name "unconnected-(IC1-NC-Pad24)") (class "Default")
      (node (ref "IC1") (pin "24") (pinfunction "NC_24") (pintype "tri_state+no_connect"))
    )
    (net (code "66") (name "unconnected-(IC1-PWM1-Pad35)") (class "Default")
      (node (ref "IC1") (pin "35") (pinfunction "PWM1_35") (pintype "output+no_connect"))
    )
    (net (code "67") (name "unconnected-(IC1-PWM2-Pad36)") (class "Default")
      (node (ref "IC1") (pin "36") (pinfunction "PWM2_36") (pintype "output+no_connect"))
    )
    (net (code "68") (name "unconnected-(IC1-RI-Pad4)") (class "Default")
      (node (ref "IC1") (pin "4") (pinfunction "RI_4") (pintype "output+no_connect"))
    )
    (net (code "69") (name "unconnected-(IC1-RTS-Pad8)") (class "Default")
      (node (ref "IC1") (pin "8") (pinfunction "RTS_8") (pintype "input+no_connect"))
    )
    (net (code "70") (name "unconnected-(IC1-SCL-Pad38)") (class "Default")
      (node (ref "IC1") (pin "38") (pinfunction "SCL_38") (pintype "bidirectional+no_connect"))
    )
    (net (code "71") (name "unconnected-(IC1-SDA-Pad37)") (class "Default")
      (node (ref "IC1") (pin "37") (pinfunction "SDA_37") (pintype "output+no_connect"))
    )
    (net (code "72") (name "unconnected-(IC1-SIM_PRESENCE-Pad34)") (class "Default")
      (node (ref "IC1") (pin "34") (pinfunction "SIM_PRESENCE_34") (pintype "input+no_connect"))
    )
    (net (code "73") (name "unconnected-(IC1-SPK_N-Pad22)") (class "Default")
      (node (ref "IC1") (pin "22") (pinfunction "SPK_N_22") (pintype "output+no_connect"))
    )
    (net (code "74") (name "unconnected-(IC1-SPK_P-Pad21)") (class "Default")
      (node (ref "IC1") (pin "21") (pinfunction "SPK_P_21") (pintype "output+no_connect"))
    )
    (net (code "75") (name "unconnected-(IC1-VRTC-Pad26)") (class "Default")
      (node (ref "IC1") (pin "26") (pinfunction "VRTC_26") (pintype "bidirectional+no_connect"))
    )
    (net (code "76") (name "unconnected-(J1-VPP-Pad6)") (class "Default")
      (node (ref "J1") (pin "6") (pinfunction "VPP_6") (pintype "passive+no_connect"))
    )
  )
)
